# rev_1.net
KiCad netlist of a schematic drawn in Altium Designer
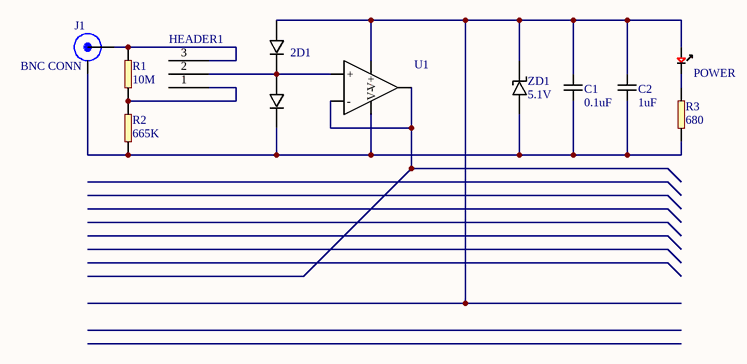
[diagram p0: rev_1.SchDoc]

(export (version "E")
  (design (tool "Eeschema 10.0.6"))
  (components
    (comp (ref "2D1")
      (value "BAT54SW-FDICT")
      (footprint "SOT-23-3")
      (libsource (lib "OpBots") (part "BAT54SW-FDICT"))
    )
    (comp (ref "C1")
      (value "Capacitor")
      (footprint "0603")
      (fields (field (name "C") "0.1uF"))
      (libsource (lib "OpBots") (part "Capacitor"))
    )
    (comp (ref "C2")
      (value "Capacitor")
      (footprint "0603")
      (fields (field (name "C") "1uF"))
      (libsource (lib "OpBots") (part "Capacitor"))
    )
    (comp (ref "HEADER1")
      (value "3x1")
      (footprint "3x1 THRU HOLES 0.1\" PITCH")
      (libsource (lib "OpBots") (part "3x1"))
    )
    (comp (ref "J1")
      (value "BNC CONN")
      (footprint "BNC THROUGH HOLE")
      (libsource (lib "OpBots") (part "A33798"))
    )
    (comp (ref "POWER") (value "LEDR") (footprint "0603 - LED") (libsource (lib "OpBots") (part "LEDR")))
    (comp (ref "R1")
      (value "Resistor")
      (footprint "0603")
      (fields (field (name "R") "10M"))
      (libsource (lib "OpBots") (part "Resistor"))
    )
    (comp (ref "R2")
      (value "Resistor")
      (footprint "0603")
      (fields (field (name "R") "665K"))
      (libsource (lib "OpBots") (part "Resistor"))
    )
    (comp (ref "R3")
      (value "Resistor")
      (footprint "0603")
      (fields (field (name "R") "680"))
      (libsource (lib "OpBots") (part "Resistor"))
    )
    (comp (ref "U1")
      (value "MCP6L9IT-E")
      (footprint "SOT-23-5")
      (libsource (lib "OpBots") (part "MCP6L9IT-E"))
    )
    (comp (ref "ZD1")
      (value "Zener")
      (fields (field (name "VOLTAGE") "5.1V"))
      (libsource (lib "OpBots") (part "Zener"))
    )
  )
  (nets
    (net (code "1") (name "Net-(HEADER1-Pad1)") (class "Default")
      (node (ref "HEADER1") (pin "1") (pintype "passive"))
      (node (ref "R1") (pin "2") (pintype "passive"))
      (node (ref "R2") (pin "1") (pintype "passive"))
    )
    (net (code "2") (name "Net-(J1-G)") (class "Default")
      (node (ref "2D1") (pin "2") (pintype "passive"))
      (node (ref "C1") (pin "2") (pintype "passive"))
      (node (ref "C2") (pin "2") (pintype "passive"))
      (node (ref "J1") (pin "1") (pinfunction "G_1") (pintype "passive"))
      (node (ref "R2") (pin "2") (pintype "passive"))
      (node (ref "R3") (pin "2") (pintype "passive"))
      (node (ref "U1") (pin "2") (pinfunction "V-_2") (pintype "passive"))
      (node (ref "ZD1") (pin "2") (pintype "passive"))
    )
    (net (code "3") (name "Net-(J1-S)") (class "Default")
      (node (ref "HEADER1") (pin "3") (pintype "passive"))
      (node (ref "J1") (pin "2") (pinfunction "S_2") (pintype "passive"))
      (node (ref "R1") (pin "1") (pintype "passive"))
    )
    (net (code "4") (name "Net-(POWER-A)") (class "Default")
      (node (ref "2D1") (pin "1") (pintype "passive"))
      (node (ref "C1") (pin "1") (pintype "passive"))
      (node (ref "C2") (pin "1") (pintype "passive"))
      (node (ref "POWER") (pin "2") (pinfunction "A_2") (pintype "passive"))
      (node (ref "U1") (pin "3") (pinfunction "V+_3") (pintype "passive"))
      (node (ref "ZD1") (pin "1") (pintype "passive"))
    )
    (net (code "5") (name "Net-(POWER-K)") (class "Default")
      (node (ref "POWER") (pin "1") (pinfunction "K_1") (pintype "passive"))
      (node (ref "R3") (pin "1") (pintype "passive"))
    )
    (net (code "6") (name "Net-(U1-+)") (class "Default")
      (node (ref "2D1") (pin "3") (pintype "passive"))
      (node (ref "HEADER1") (pin "2") (pintype "passive"))
      (node (ref "U1") (pin "3") (pinfunction "+_3") (pintype "passive"))
    )
    (net (code "7") (name "Net-(U1--)") (class "Default")
      (node (ref "U1") (pin "1") (pinfunction "OUT_1") (pintype "passive"))
      (node (ref "U1") (pin "4") (pinfunction "-_4") (pintype "passive"))
    )
  )
)
